# v0_2_0.net
KiCad netlist of a schematic drawn in EAGLE
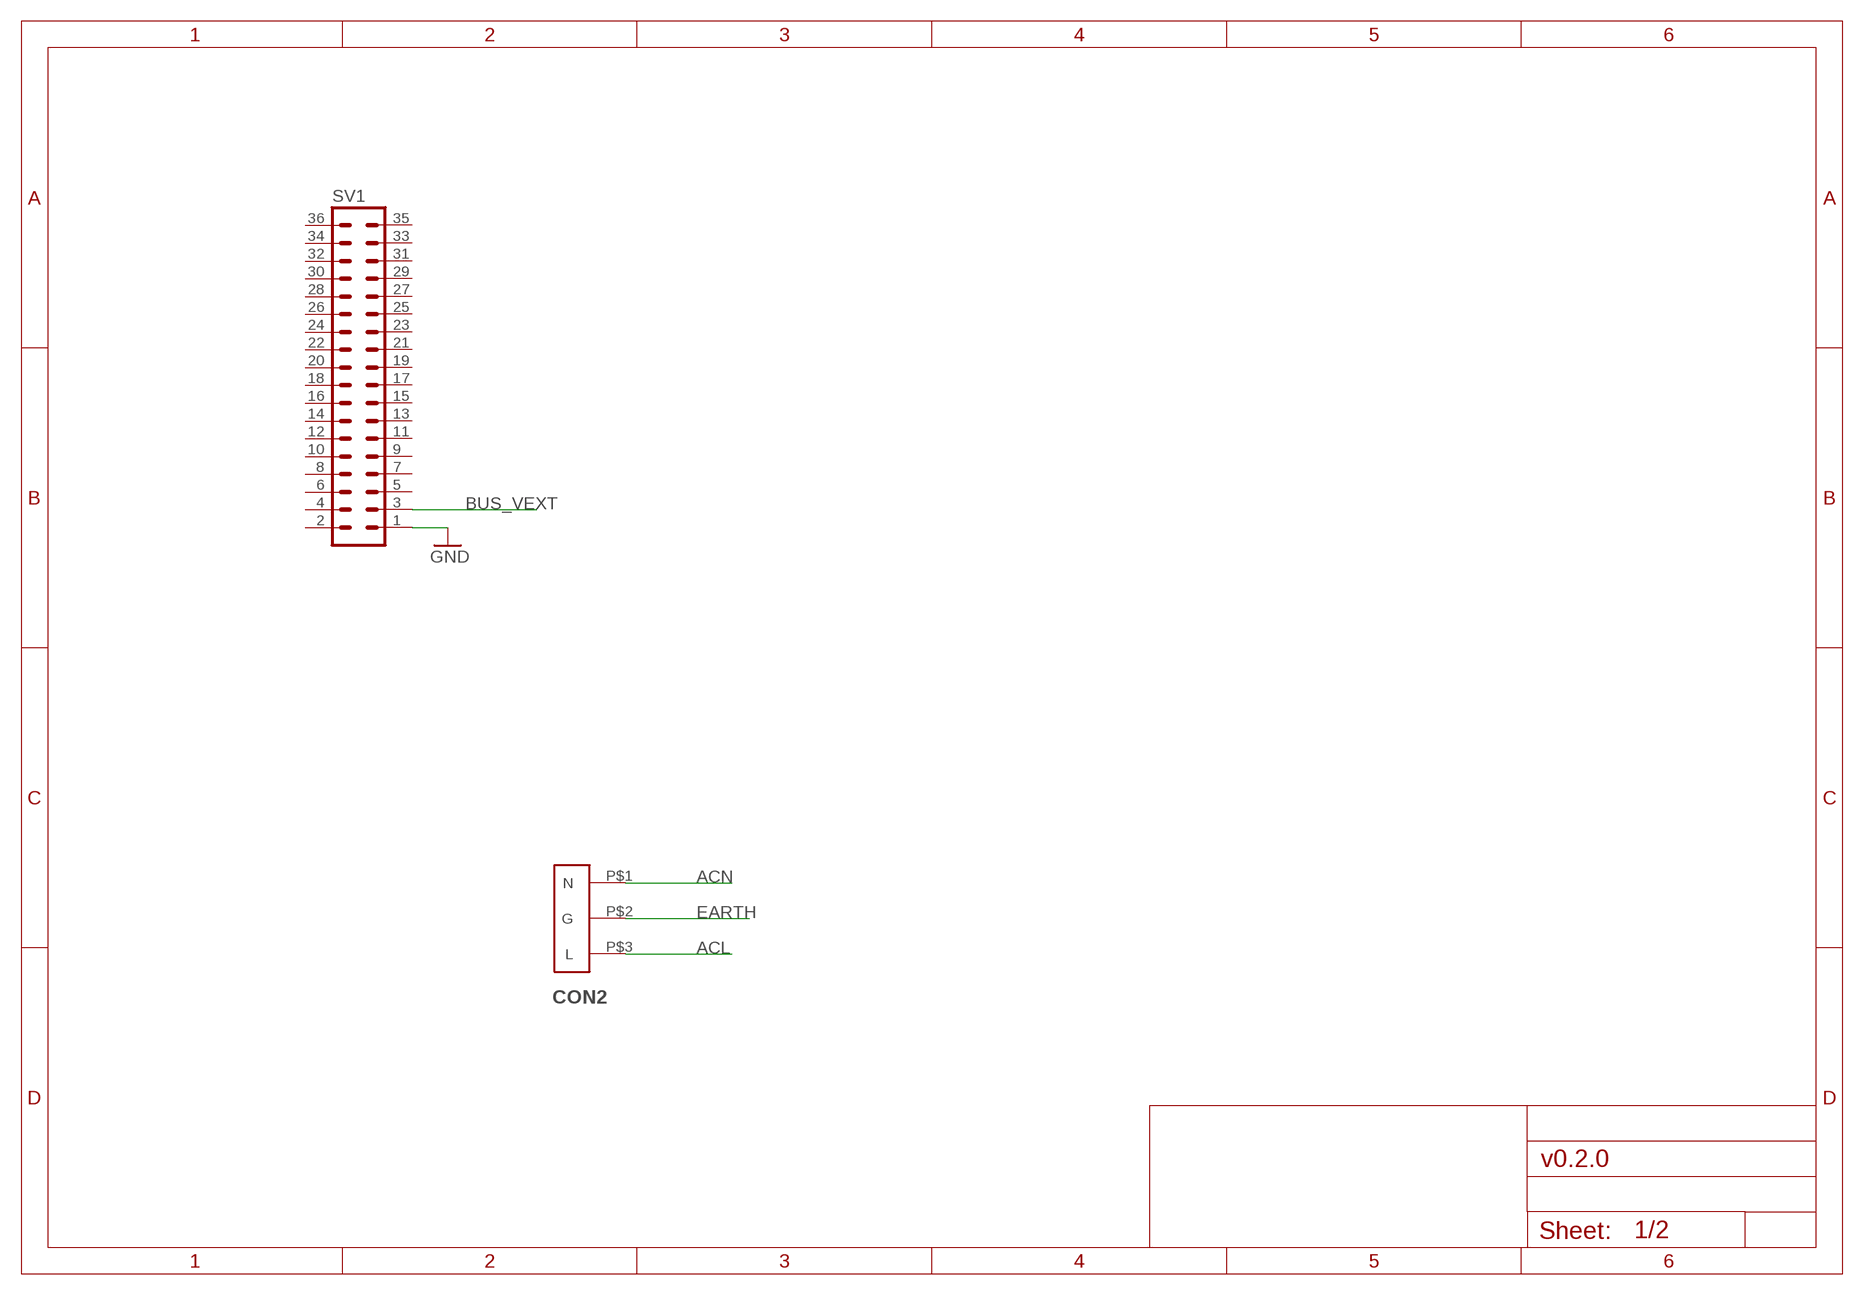
[diagram p0: schematic, sheet 1]
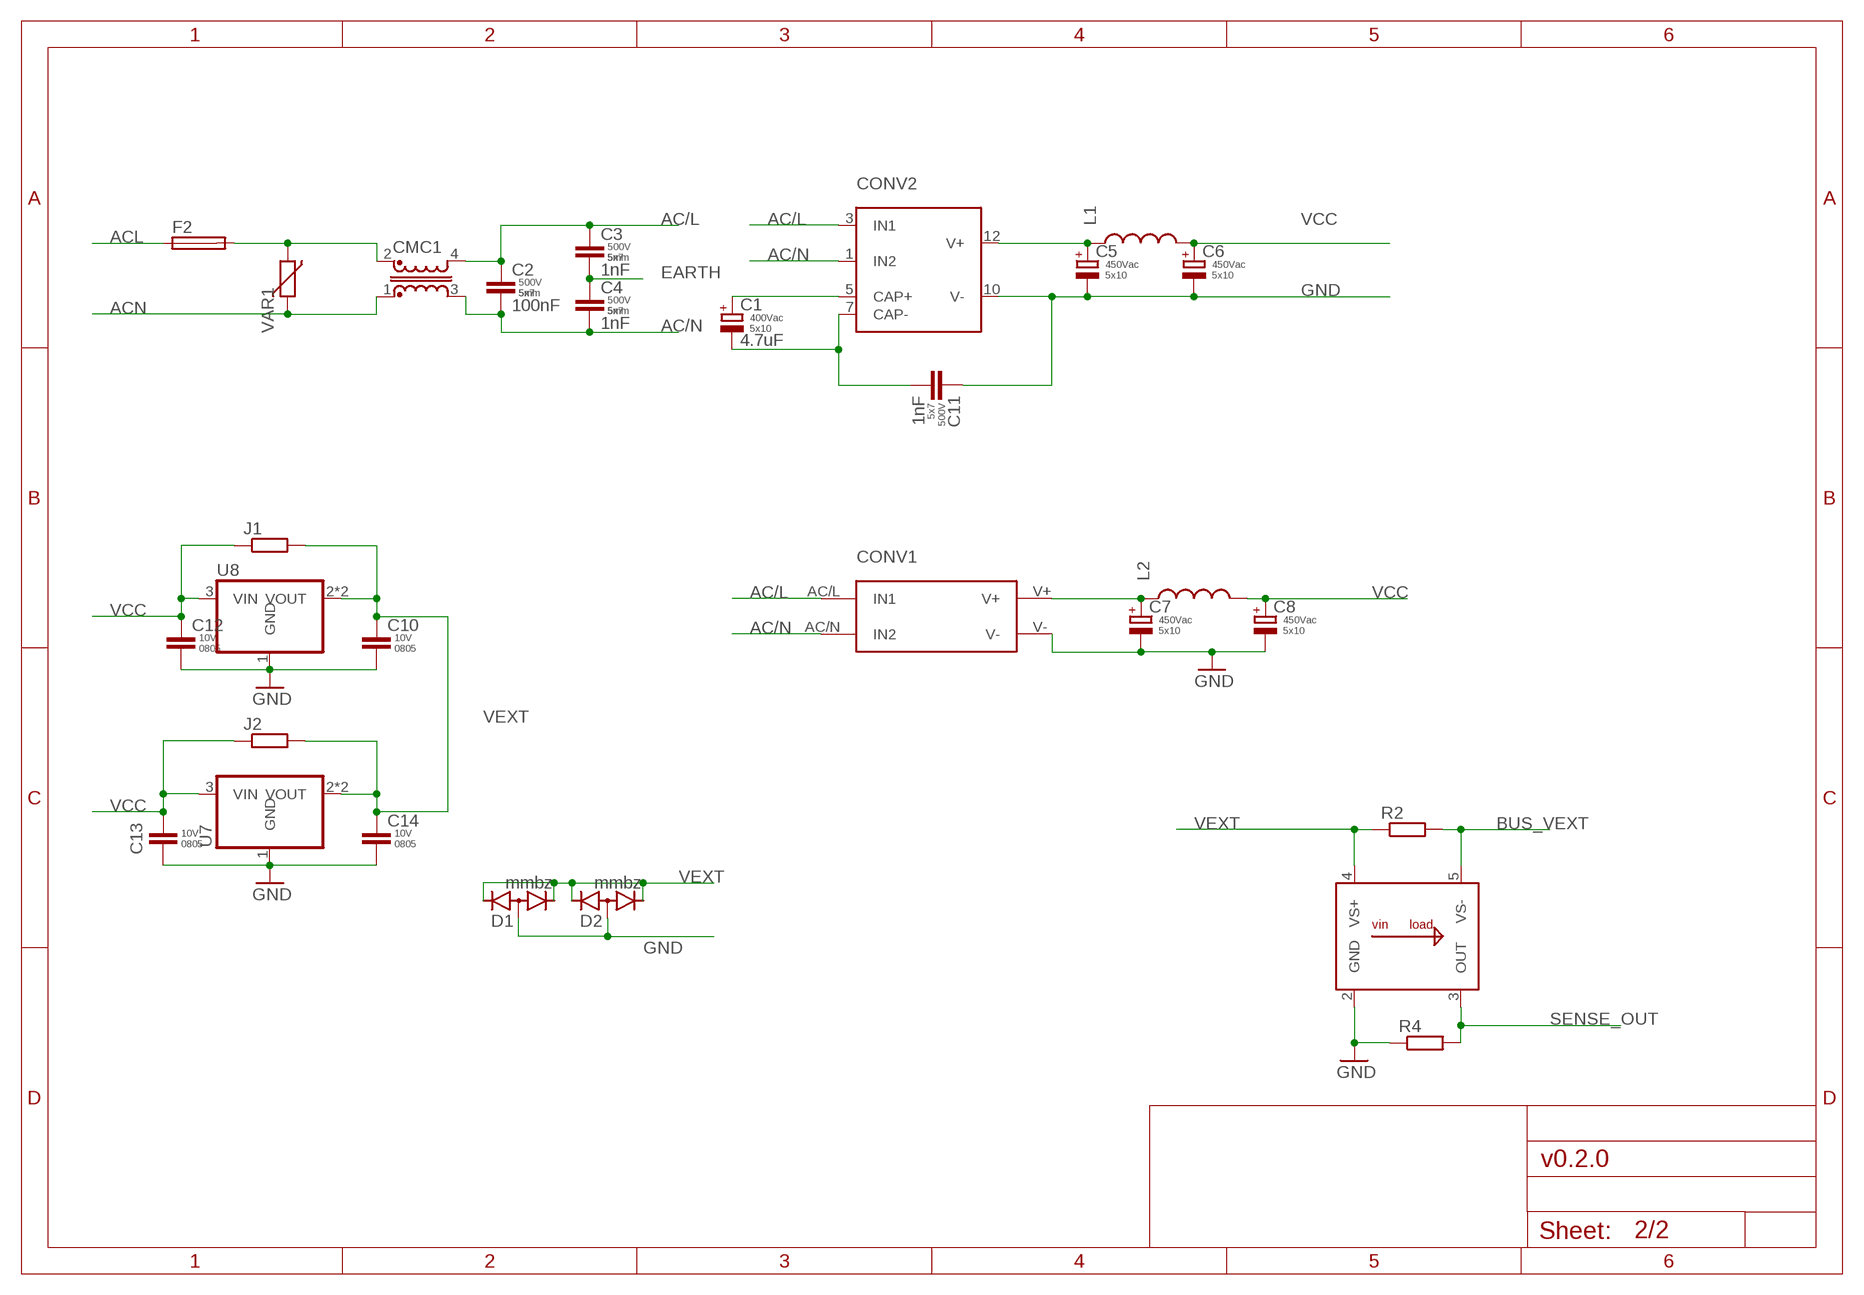
[diagram p1: schematic, sheet 2]

(export (version "E")
  (design (tool "Eeschema 10.0.6"))
  (components
    (comp (ref "C1")
      (value "4.7uF")
      (footprint "eagle-import:CAPPRD508W65D1000H1600B")
      (fields
        (field (name "PACKAGE") "5x10")
        (field (name "RATING") "450Vac")
        (field (name "RATING_1") "400Vac")
      )
      (libsource (lib "eagle-import") (part "CAP-POL-5PX10WX16H"))
    )
    (comp (ref "C2")
      (value "100nF")
      (footprint "eagle-import:C050-025X075")
      (fields
        (field (name "RATING") "500V")
        (field (name "DIMENSIONS") "5mm")
        (field (name "RATING_1") "500V")
      )
      (libsource (lib "eagle-import") (part "CAP-P5W6H8T2.5"))
    )
    (comp (ref "C3")
      (value "1nF")
      (footprint "eagle-import:C050-025X075")
      (fields
        (field (name "RATING") "500V")
        (field (name "DIMENSIONS") "5mm")
        (field (name "RATING_1") "500V")
      )
      (libsource (lib "eagle-import") (part "CAP-P5W6H8T2.5"))
    )
    (comp (ref "C4")
      (value "1nF")
      (footprint "eagle-import:C050-025X075")
      (fields
        (field (name "RATING") "500V")
        (field (name "DIMENSIONS") "5mm")
        (field (name "RATING_1") "500V")
      )
      (libsource (lib "eagle-import") (part "CAP-P5W6H8T2.5"))
    )
    (comp (ref "C5")
      (value "CAP-POL-5PX10WX16H")
      (footprint "eagle-import:CAPPRD508W65D1000H1600B")
      (libsource (lib "eagle-import") (part "CAP-POL-5PX10WX16H"))
    )
    (comp (ref "C6")
      (value "CAP-POL-5PX10WX16H")
      (footprint "eagle-import:CAPPRD508W65D1000H1600B")
      (libsource (lib "eagle-import") (part "CAP-POL-5PX10WX16H"))
    )
    (comp (ref "C7")
      (value "CAP-POL-5PX10WX16H")
      (footprint "eagle-import:CAPPRD508W65D1000H1600B")
      (libsource (lib "eagle-import") (part "CAP-POL-5PX10WX16H"))
    )
    (comp (ref "C8")
      (value "CAP-POL-5PX10WX16H")
      (footprint "eagle-import:CAPPRD508W65D1000H1600B")
      (libsource (lib "eagle-import") (part "CAP-POL-5PX10WX16H"))
    )
    (comp (ref "C10")
      (value "CAP-0805")
      (footprint "eagle-import:C0805")
      (libsource (lib "eagle-import") (part "CAP-0805"))
    )
    (comp (ref "C11")
      (value "1nF")
      (footprint "eagle-import:C050-025X075")
      (fields (field (name "RATING") "500V") (field (name "PACKAGE") "5x7"))
      (libsource (lib "eagle-import") (part "CAP-P5W6H8T2.5"))
    )
    (comp (ref "C12")
      (value "CAP-0805")
      (footprint "eagle-import:C0805")
      (libsource (lib "eagle-import") (part "CAP-0805"))
    )
    (comp (ref "C13")
      (value "CAP-0805")
      (footprint "eagle-import:C0805")
      (libsource (lib "eagle-import") (part "CAP-0805"))
    )
    (comp (ref "C14")
      (value "CAP-0805")
      (footprint "eagle-import:C0805")
      (libsource (lib "eagle-import") (part "CAP-0805"))
    )
    (comp (ref "CMC1")
      (value "DLD-302U-1A")
      (footprint "eagle-import:DLD")
      (libsource (lib "eagle-import") (part "DLD-302U-1A"))
    )
    (comp (ref "CONV1")
      (value "IRM-03-12V")
      (footprint "eagle-import:IRM-03")
      (libsource (lib "eagle-import") (part "IRM-03-12V"))
    )
    (comp (ref "CONV2")
      (value "AMEOF312SJZ")
      (footprint "eagle-import:AMEOF3-JZ")
      (libsource (lib "eagle-import") (part "AMEOF312SJZ"))
    )
    (comp (ref "D1")
      (value "mmbz")
      (footprint "eagle-import:SOT23")
      (libsource (lib "eagle-import") (part "DIODE-2CA|ACSOT23"))
    )
    (comp (ref "D2")
      (value "mmbz")
      (footprint "eagle-import:SOT23")
      (libsource (lib "eagle-import") (part "DIODE-2CA|ACSOT23"))
    )
    (comp (ref "F2")
      (value "ZH8")
      (footprint "eagle-import:ZH8X2")
      (libsource (lib "eagle-import") (part "ZH8"))
    )
    (comp (ref "IC1")
      (value "ZXCT1021")
      (footprint "eagle-import:SOT95P240X110-5")
      (libsource (lib "eagle-import") (part "ZXCT1021"))
    )
    (comp (ref "J1")
      (value "R-EU_R0805")
      (footprint "eagle-import:R0805")
      (libsource (lib "eagle-import") (part "R-EU_R0805"))
    )
    (comp (ref "J2")
      (value "R-EU_R0805")
      (footprint "eagle-import:R0805")
      (libsource (lib "eagle-import") (part "R-EU_R0805"))
    )
    (comp (ref "L1")
      (value "COIL0608-0.022")
      (footprint "eagle-import:COIL0608")
      (libsource (lib "eagle-import") (part "COIL0608-0.022"))
    )
    (comp (ref "L2")
      (value "COIL0608-0.022")
      (footprint "eagle-import:COIL0608")
      (libsource (lib "eagle-import") (part "COIL0608-0.022"))
    )
    (comp (ref "R2")
      (value "R-EU_R0805")
      (footprint "eagle-import:R0805")
      (libsource (lib "eagle-import") (part "R-EU_R0805"))
    )
    (comp (ref "R4")
      (value "R-EU_R0603")
      (footprint "eagle-import:R0603")
      (libsource (lib "eagle-import") (part "R-EU_R0603"))
    )
    (comp (ref "U7")
      (value "LD1117S50")
      (footprint "eagle-import:SOT230P700X180-4")
      (libsource (lib "eagle-import") (part "LD1117S50"))
    )
    (comp (ref "U8")
      (value "LD1117S50")
      (footprint "eagle-import:SOT230P700X180-4")
      (libsource (lib "eagle-import") (part "LD1117S50"))
    )
    (comp (ref "VAR1")
      (value "S14K250")
      (footprint "eagle-import:C7.5B4")
      (libsource (lib "eagle-import") (part "S14K250"))
    )
    (comp (ref "CON2")
      (value "4300.0101")
      (footprint "eagle-import:IEC-C6")
      (libsource (lib "eagle-import") (part "4300.0101"))
    )
    (comp (ref "SV1")
      (value "MA18-2")
      (footprint "eagle-import:MA18-2")
      (libsource (lib "eagle-import") (part "MA18-2"))
    )
  )
  (nets
    (net (code "1") (name "ACL") (class "Default")
      (node (ref "CON2") (pin "P$3") (pinfunction "L_P$3") (pintype "bidirectional"))
      (node (ref "F2") (pin "1") (pinfunction "1_1") (pintype "passive"))
      (node (ref "F2") (pin "1A") (pinfunction "1_1A") (pintype "passive"))
    )
    (net (code "2") (name "ACN") (class "Default")
      (node (ref "CMC1") (pin "1") (pinfunction "1_1") (pintype "passive"))
      (node (ref "CON2") (pin "P$1") (pinfunction "N_P$1") (pintype "bidirectional"))
      (node (ref "VAR1") (pin "1") (pinfunction "1_1") (pintype "passive"))
    )
    (net (code "3") (name "AC{slash}L") (class "Default")
      (node (ref "C2") (pin "1") (pinfunction "1_1") (pintype "passive"))
      (node (ref "C3") (pin "1") (pinfunction "1_1") (pintype "passive"))
      (node (ref "CMC1") (pin "4") (pinfunction "4_4") (pintype "passive"))
      (node (ref "CONV1") (pin "AC/L") (pinfunction "IN1_AC/L") (pintype "bidirectional"))
      (node (ref "CONV2") (pin "3") (pinfunction "IN1_3") (pintype "bidirectional"))
    )
    (net (code "4") (name "AC{slash}N") (class "Default")
      (node (ref "C2") (pin "2") (pinfunction "2_2") (pintype "passive"))
      (node (ref "C4") (pin "2") (pinfunction "2_2") (pintype "passive"))
      (node (ref "CMC1") (pin "3") (pinfunction "3_3") (pintype "passive"))
      (node (ref "CONV1") (pin "AC/N") (pinfunction "IN2_AC/N") (pintype "bidirectional"))
      (node (ref "CONV2") (pin "1") (pinfunction "IN2_1") (pintype "bidirectional"))
    )
    (net (code "5") (name "BUS_VEXT") (class "Default")
      (node (ref "IC1") (pin "5") (pinfunction "VS-_5") (pintype "bidirectional"))
      (node (ref "R2") (pin "2") (pinfunction "2_2") (pintype "passive"))
      (node (ref "SV1") (pin "3") (pinfunction "3_3") (pintype "passive"))
    )
    (net (code "6") (name "EARTH") (class "Default")
      (node (ref "C3") (pin "2") (pinfunction "2_2") (pintype "passive"))
      (node (ref "C4") (pin "1") (pinfunction "1_1") (pintype "passive"))
      (node (ref "CON2") (pin "P$2") (pinfunction "G_P$2") (pintype "bidirectional"))
    )
    (net (code "7") (name "GND") (class "Default")
      (node (ref "C10") (pin "2") (pinfunction "2_2") (pintype "passive"))
      (node (ref "C11") (pin "1") (pinfunction "1_1") (pintype "passive"))
      (node (ref "C12") (pin "2") (pinfunction "2_2") (pintype "passive"))
      (node (ref "C13") (pin "2") (pinfunction "2_2") (pintype "passive"))
      (node (ref "C14") (pin "2") (pinfunction "2_2") (pintype "passive"))
      (node (ref "C5") (pin "2") (pinfunction "-_2") (pintype "passive"))
      (node (ref "C6") (pin "2") (pinfunction "-_2") (pintype "passive"))
      (node (ref "C7") (pin "2") (pinfunction "-_2") (pintype "passive"))
      (node (ref "C8") (pin "2") (pinfunction "-_2") (pintype "passive"))
      (node (ref "CONV1") (pin "V-") (pinfunction "V-_V-") (pintype "bidirectional"))
      (node (ref "CONV2") (pin "10") (pinfunction "V-_10") (pintype "bidirectional"))
      (node (ref "D1") (pin "3") (pinfunction "A_3") (pintype "passive"))
      (node (ref "D2") (pin "3") (pinfunction "A_3") (pintype "passive"))
      (node (ref "IC1") (pin "2") (pinfunction "GND_2") (pintype "bidirectional"))
      (node (ref "R4") (pin "1") (pinfunction "1_1") (pintype "passive"))
      (node (ref "SV1") (pin "1") (pinfunction "1_1") (pintype "passive"))
      (node (ref "U7") (pin "1") (pinfunction "GND_1") (pintype "power_in"))
      (node (ref "U8") (pin "1") (pinfunction "GND_1") (pintype "power_in"))
    )
    (net (code "8") (name "Net-(C1-+)") (class "Default")
      (node (ref "C1") (pin "1") (pinfunction "+_1") (pintype "passive"))
      (node (ref "CONV2") (pin "5") (pinfunction "CAP+_5") (pintype "bidirectional"))
    )
    (net (code "9") (name "Net-(C1--)") (class "Default")
      (node (ref "C1") (pin "2") (pinfunction "-_2") (pintype "passive"))
      (node (ref "C11") (pin "2") (pinfunction "2_2") (pintype "passive"))
      (node (ref "CONV2") (pin "7") (pinfunction "CAP-_7") (pintype "bidirectional"))
    )
    (net (code "10") (name "Net-(C5-+)") (class "Default")
      (node (ref "C5") (pin "1") (pinfunction "+_1") (pintype "passive"))
      (node (ref "CONV2") (pin "12") (pinfunction "V+_12") (pintype "bidirectional"))
      (node (ref "L1") (pin "P$1") (pinfunction "1_P$1") (pintype "passive"))
    )
    (net (code "11") (name "Net-(C7-+)") (class "Default")
      (node (ref "C7") (pin "1") (pinfunction "+_1") (pintype "passive"))
      (node (ref "CONV1") (pin "V+") (pinfunction "V+_V+") (pintype "bidirectional"))
      (node (ref "L2") (pin "P$1") (pinfunction "1_P$1") (pintype "passive"))
    )
    (net (code "12") (name "Net-(CMC1-Pad2)") (class "Default")
      (node (ref "CMC1") (pin "2") (pinfunction "2_2") (pintype "passive"))
      (node (ref "F2") (pin "2") (pinfunction "2_2") (pintype "passive"))
      (node (ref "F2") (pin "2A") (pinfunction "2_2A") (pintype "passive"))
      (node (ref "VAR1") (pin "2") (pinfunction "2_2") (pintype "passive"))
    )
    (net (code "13") (name "SENSE_OUT") (class "Default")
      (node (ref "IC1") (pin "3") (pinfunction "OUT_3") (pintype "bidirectional"))
      (node (ref "R4") (pin "2") (pinfunction "2_2") (pintype "passive"))
    )
    (net (code "14") (name "VCC") (class "Default")
      (node (ref "C12") (pin "1") (pinfunction "1_1") (pintype "passive"))
      (node (ref "C13") (pin "1") (pinfunction "1_1") (pintype "passive"))
      (node (ref "C6") (pin "1") (pinfunction "+_1") (pintype "passive"))
      (node (ref "C8") (pin "1") (pinfunction "+_1") (pintype "passive"))
      (node (ref "J1") (pin "1") (pinfunction "1_1") (pintype "passive"))
      (node (ref "J2") (pin "1") (pinfunction "1_1") (pintype "passive"))
      (node (ref "L1") (pin "P$2") (pinfunction "2_P$2") (pintype "passive"))
      (node (ref "L2") (pin "P$2") (pinfunction "2_P$2") (pintype "passive"))
      (node (ref "U7") (pin "3") (pinfunction "VIN_3") (pintype "input"))
      (node (ref "U8") (pin "3") (pinfunction "VIN_3") (pintype "input"))
    )
    (net (code "15") (name "VEXT") (class "Default")
      (node (ref "C10") (pin "1") (pinfunction "1_1") (pintype "passive"))
      (node (ref "C14") (pin "1") (pinfunction "1_1") (pintype "passive"))
      (node (ref "D1") (pin "1") (pinfunction "K1_1") (pintype "passive"))
      (node (ref "D1") (pin "2") (pinfunction "K2_2") (pintype "passive"))
      (node (ref "D2") (pin "1") (pinfunction "K1_1") (pintype "passive"))
      (node (ref "D2") (pin "2") (pinfunction "K2_2") (pintype "passive"))
      (node (ref "IC1") (pin "4") (pinfunction "VS+_4") (pintype "bidirectional"))
      (node (ref "J1") (pin "2") (pinfunction "2_2") (pintype "passive"))
      (node (ref "J2") (pin "2") (pinfunction "2_2") (pintype "passive"))
      (node (ref "R2") (pin "1") (pinfunction "1_1") (pintype "passive"))
      (node (ref "U7") (pin "2") (pinfunction "VOUT_2") (pintype "output"))
      (node (ref "U7") (pin "4") (pinfunction "VOUT_4") (pintype "output"))
      (node (ref "U8") (pin "2") (pinfunction "VOUT_2") (pintype "output"))
      (node (ref "U8") (pin "4") (pinfunction "VOUT_4") (pintype "output"))
    )
    (net (code "16") (name "unconnected-(SV1-Pad2)") (class "Default")
      (node (ref "SV1") (pin "2") (pinfunction "2_2") (pintype "passive"))
    )
    (net (code "17") (name "unconnected-(SV1-Pad4)") (class "Default")
      (node (ref "SV1") (pin "4") (pinfunction "4_4") (pintype "passive"))
    )
    (net (code "18") (name "unconnected-(SV1-Pad5)") (class "Default")
      (node (ref "SV1") (pin "5") (pinfunction "5_5") (pintype "passive"))
    )
    (net (code "19") (name "unconnected-(SV1-Pad6)") (class "Default")
      (node (ref "SV1") (pin "6") (pinfunction "6_6") (pintype "passive"))
    )
    (net (code "20") (name "unconnected-(SV1-Pad7)") (class "Default")
      (node (ref "SV1") (pin "7") (pinfunction "7_7") (pintype "passive"))
    )
    (net (code "21") (name "unconnected-(SV1-Pad8)") (class "Default")
      (node (ref "SV1") (pin "8") (pinfunction "8_8") (pintype "passive"))
    )
    (net (code "22") (name "unconnected-(SV1-Pad9)") (class "Default")
      (node (ref "SV1") (pin "9") (pinfunction "9_9") (pintype "passive"))
    )
    (net (code "23") (name "unconnected-(SV1-Pad10)") (class "Default")
      (node (ref "SV1") (pin "10") (pinfunction "10_10") (pintype "passive"))
    )
    (net (code "24") (name "unconnected-(SV1-Pad11)") (class "Default")
      (node (ref "SV1") (pin "11") (pinfunction "11_11") (pintype "passive"))
    )
    (net (code "25") (name "unconnected-(SV1-Pad12)") (class "Default")
      (node (ref "SV1") (pin "12") (pinfunction "12_12") (pintype "passive"))
    )
    (net (code "26") (name "unconnected-(SV1-Pad13)") (class "Default")
      (node (ref "SV1") (pin "13") (pinfunction "13_13") (pintype "passive"))
    )
    (net (code "27") (name "unconnected-(SV1-Pad14)") (class "Default")
      (node (ref "SV1") (pin "14") (pinfunction "14_14") (pintype "passive"))
    )
    (net (code "28") (name "unconnected-(SV1-Pad15)") (class "Default")
      (node (ref "SV1") (pin "15") (pinfunction "15_15") (pintype "passive"))
    )
    (net (code "29") (name "unconnected-(SV1-Pad16)") (class "Default")
      (node (ref "SV1") (pin "16") (pinfunction "16_16") (pintype "passive"))
    )
    (net (code "30") (name "unconnected-(SV1-Pad17)") (class "Default")
      (node (ref "SV1") (pin "17") (pinfunction "17_17") (pintype "passive"))
    )
    (net (code "31") (name "unconnected-(SV1-Pad18)") (class "Default")
      (node (ref "SV1") (pin "18") (pinfunction "18_18") (pintype "passive"))
    )
    (net (code "32") (name "unconnected-(SV1-Pad19)") (class "Default")
      (node (ref "SV1") (pin "19") (pinfunction "19_19") (pintype "passive"))
    )
    (net (code "33") (name "unconnected-(SV1-Pad20)") (class "Default")
      (node (ref "SV1") (pin "20") (pinfunction "20_20") (pintype "passive"))
    )
    (net (code "34") (name "unconnected-(SV1-Pad21)") (class "Default")
      (node (ref "SV1") (pin "21") (pinfunction "21_21") (pintype "passive"))
    )
    (net (code "35") (name "unconnected-(SV1-Pad22)") (class "Default")
      (node (ref "SV1") (pin "22") (pinfunction "22_22") (pintype "passive"))
    )
    (net (code "36") (name "unconnected-(SV1-Pad23)") (class "Default")
      (node (ref "SV1") (pin "23") (pinfunction "23_23") (pintype "passive"))
    )
    (net (code "37") (name "unconnected-(SV1-Pad24)") (class "Default")
      (node (ref "SV1") (pin "24") (pinfunction "24_24") (pintype "passive"))
    )
    (net (code "38") (name "unconnected-(SV1-Pad25)") (class "Default")
      (node (ref "SV1") (pin "25") (pinfunction "25_25") (pintype "passive"))
    )
    (net (code "39") (name "unconnected-(SV1-Pad26)") (class "Default")
      (node (ref "SV1") (pin "26") (pinfunction "26_26") (pintype "passive"))
    )
    (net (code "40") (name "unconnected-(SV1-Pad27)") (class "Default")
      (node (ref "SV1") (pin "27") (pinfunction "27_27") (pintype "passive"))
    )
    (net (code "41") (name "unconnected-(SV1-Pad28)") (class "Default")
      (node (ref "SV1") (pin "28") (pinfunction "28_28") (pintype "passive"))
    )
    (net (code "42") (name "unconnected-(SV1-Pad29)") (class "Default")
      (node (ref "SV1") (pin "29") (pinfunction "29_29") (pintype "passive"))
    )
    (net (code "43") (name "unconnected-(SV1-Pad30)") (class "Default")
      (node (ref "SV1") (pin "30") (pinfunction "30_30") (pintype "passive"))
    )
    (net (code "44") (name "unconnected-(SV1-Pad31)") (class "Default")
      (node (ref "SV1") (pin "31") (pinfunction "31_31") (pintype "passive"))
    )
    (net (code "45") (name "unconnected-(SV1-Pad32)") (class "Default")
      (node (ref "SV1") (pin "32") (pinfunction "32_32") (pintype "passive"))
    )
    (net (code "46") (name "unconnected-(SV1-Pad33)") (class "Default")
      (node (ref "SV1") (pin "33") (pinfunction "33_33") (pintype "passive"))
    )
    (net (code "47") (name "unconnected-(SV1-Pad34)") (class "Default")
      (node (ref "SV1") (pin "34") (pinfunction "34_34") (pintype "passive"))
    )
    (net (code "48") (name "unconnected-(SV1-Pad35)") (class "Default")
      (node (ref "SV1") (pin "35") (pinfunction "35_35") (pintype "passive"))
    )
    (net (code "49") (name "unconnected-(SV1-Pad36)") (class "Default")
      (node (ref "SV1") (pin "36") (pinfunction "36_36") (pintype "passive"))
    )
  )
)
